# Headphone-Amplifier-ClassAB-alt2.net
KiCad netlist of a schematic drawn in EAGLE
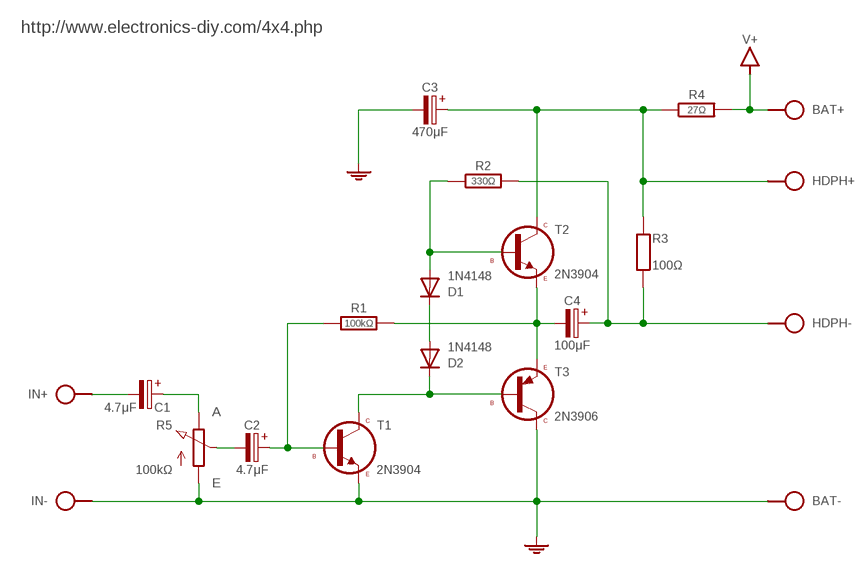
[diagram p0: schematic, sheet 1]

(export (version "E")
  (design (tool "Eeschema 10.0.6"))
  (components
    (comp (ref "BAT")
      (value "SPAD+-+-")
      (footprint "eagle-import:SPAD+-")
      (libsource (lib "eagle-import") (part "SPAD+-+-"))
    )
    (comp (ref "C1")
      (value "4.7μF")
      (footprint "eagle-import:E2,5-4")
      (libsource (lib "eagle-import") (part "CPOL-HE2,5-4"))
    )
    (comp (ref "C2")
      (value "4.7μF")
      (footprint "eagle-import:E2,5-3")
      (libsource (lib "eagle-import") (part "CPOLE2,5-3"))
    )
    (comp (ref "C3")
      (value "470μF")
      (footprint "eagle-import:E5-5")
      (libsource (lib "eagle-import") (part "CPOLE5-5"))
    )
    (comp (ref "C4")
      (value "100μF")
      (footprint "eagle-import:E2,5-5")
      (libsource (lib "eagle-import") (part "CPOLE2.5-5"))
    )
    (comp (ref "D1")
      (value "1N4148")
      (footprint "eagle-import:DO34-5-V")
      (libsource (lib "eagle-import") (part "DIODE34-5-V"))
    )
    (comp (ref "D2")
      (value "1N4148")
      (footprint "eagle-import:DO34-5V")
      (libsource (lib "eagle-import") (part "DIODE34-5V"))
    )
    (comp (ref "HDPH")
      (value "SPAD+--+")
      (footprint "eagle-import:SPAD-+")
      (libsource (lib "eagle-import") (part "SPAD+--+"))
    )
    (comp (ref "IN")
      (value "SPAD+--+")
      (footprint "eagle-import:SPAD-+")
      (libsource (lib "eagle-import") (part "SPAD+--+"))
    )
    (comp (ref "R1")
      (value "100kΩ")
      (footprint "eagle-import:0204_10")
      (libsource (lib "eagle-import") (part "R-H0204/10"))
    )
    (comp (ref "R2")
      (value "330Ω")
      (footprint "eagle-import:0204_10")
      (libsource (lib "eagle-import") (part "R-H0204/10"))
    )
    (comp (ref "R3")
      (value "100Ω")
      (footprint "eagle-import:0204_10")
      (libsource (lib "eagle-import") (part "R0204/10"))
    )
    (comp (ref "R4")
      (value "27Ω")
      (footprint "eagle-import:0204_2.54")
      (libsource (lib "eagle-import") (part "R-H0204/2.54"))
    )
    (comp (ref "R5")
      (value "100kΩ")
      (footprint "eagle-import:CONN-3P")
      (libsource (lib "eagle-import") (part "POT-3P"))
    )
    (comp (ref "T1")
      (value "2N3904")
      (footprint "eagle-import:TO92")
      (libsource (lib "eagle-import") (part "2N3904"))
    )
    (comp (ref "T2")
      (value "2N3904")
      (footprint "eagle-import:TO92")
      (libsource (lib "eagle-import") (part "2N3904"))
    )
    (comp (ref "T3")
      (value "2N3906")
      (footprint "eagle-import:TO92")
      (libsource (lib "eagle-import") (part "2N3906"))
    )
  )
  (nets
    (net (code "1") (name "GND") (class "Default")
      (node (ref "BAT") (pin "1") (pinfunction "P$1_1") (pintype "passive"))
      (node (ref "C3") (pin "-") (pinfunction "-_-") (pintype "passive"))
      (node (ref "IN") (pin "1") (pinfunction "P$1_1") (pintype "passive"))
      (node (ref "R5") (pin "1") (pinfunction "A_1") (pintype "passive"))
      (node (ref "T1") (pin "1") (pinfunction "E_1") (pintype "passive"))
      (node (ref "T3") (pin "3") (pinfunction "C_3") (pintype "passive"))
    )
    (net (code "2") (name "Net-(D1-PadC)") (class "Default")
      (node (ref "D1") (pin "C") (pinfunction "C_C") (pintype "passive"))
      (node (ref "D2") (pin "A") (pinfunction "A_A") (pintype "passive"))
    )
    (net (code "3") (name "Net-(HDPHA-P$1)") (class "Default")
      (node (ref "C3") (pin "+") (pinfunction "+_+") (pintype "passive"))
      (node (ref "HDPH") (pin "2") (pinfunction "P$1_2") (pintype "passive"))
      (node (ref "R3") (pin "1") (pinfunction "2_1") (pintype "passive"))
      (node (ref "R4") (pin "1") (pinfunction "1_1") (pintype "passive"))
      (node (ref "T2") (pin "3") (pinfunction "C_3") (pintype "passive"))
    )
    (net (code "4") (name "Net-(HDPHB-P$1)") (class "Default")
      (node (ref "C4") (pin "+") (pinfunction "+_+") (pintype "passive"))
      (node (ref "HDPH") (pin "1") (pinfunction "P$1_1") (pintype "passive"))
      (node (ref "R2") (pin "2") (pinfunction "2_2") (pintype "passive"))
      (node (ref "R3") (pin "2") (pinfunction "1_2") (pintype "passive"))
    )
    (net (code "5") (name "Net-(INA-P$1)") (class "Default")
      (node (ref "C1") (pin "-") (pinfunction "-_-") (pintype "passive"))
      (node (ref "IN") (pin "2") (pinfunction "P$1_2") (pintype "passive"))
    )
    (net (code "6") (name "Net-(R5-E)") (class "Default")
      (node (ref "C1") (pin "+") (pinfunction "+_+") (pintype "passive"))
      (node (ref "R5") (pin "3") (pinfunction "E_3") (pintype "passive"))
    )
    (net (code "7") (name "Net-(R5-S)") (class "Default")
      (node (ref "C2") (pin "-") (pinfunction "-_-") (pintype "passive"))
      (node (ref "R5") (pin "2") (pinfunction "S_2") (pintype "passive"))
    )
    (net (code "8") (name "Net-(T1-B)") (class "Default")
      (node (ref "C2") (pin "+") (pinfunction "+_+") (pintype "passive"))
      (node (ref "R1") (pin "1") (pinfunction "1_1") (pintype "passive"))
      (node (ref "T1") (pin "2") (pinfunction "B_2") (pintype "passive"))
    )
    (net (code "9") (name "Net-(T1-C)") (class "Default")
      (node (ref "D2") (pin "C") (pinfunction "C_C") (pintype "passive"))
      (node (ref "T1") (pin "3") (pinfunction "C_3") (pintype "passive"))
      (node (ref "T3") (pin "2") (pinfunction "B_2") (pintype "passive"))
    )
    (net (code "10") (name "Net-(T2-B)") (class "Default")
      (node (ref "D1") (pin "A") (pinfunction "A_A") (pintype "passive"))
      (node (ref "R2") (pin "1") (pinfunction "1_1") (pintype "passive"))
      (node (ref "T2") (pin "2") (pinfunction "B_2") (pintype "passive"))
    )
    (net (code "11") (name "Net-(T2-E)") (class "Default")
      (node (ref "C4") (pin "-") (pinfunction "-_-") (pintype "passive"))
      (node (ref "R1") (pin "2") (pinfunction "2_2") (pintype "passive"))
      (node (ref "T2") (pin "1") (pinfunction "E_1") (pintype "passive"))
      (node (ref "T3") (pin "1") (pinfunction "E_1") (pintype "passive"))
    )
    (net (code "12") (name "V+") (class "Default")
      (node (ref "BAT") (pin "2") (pinfunction "P$1_2") (pintype "passive"))
      (node (ref "R4") (pin "2") (pinfunction "2_2") (pintype "passive"))
    )
  )
)
